# Truss-Power-V3-B.net
KiCad netlist of a schematic drawn in EAGLE
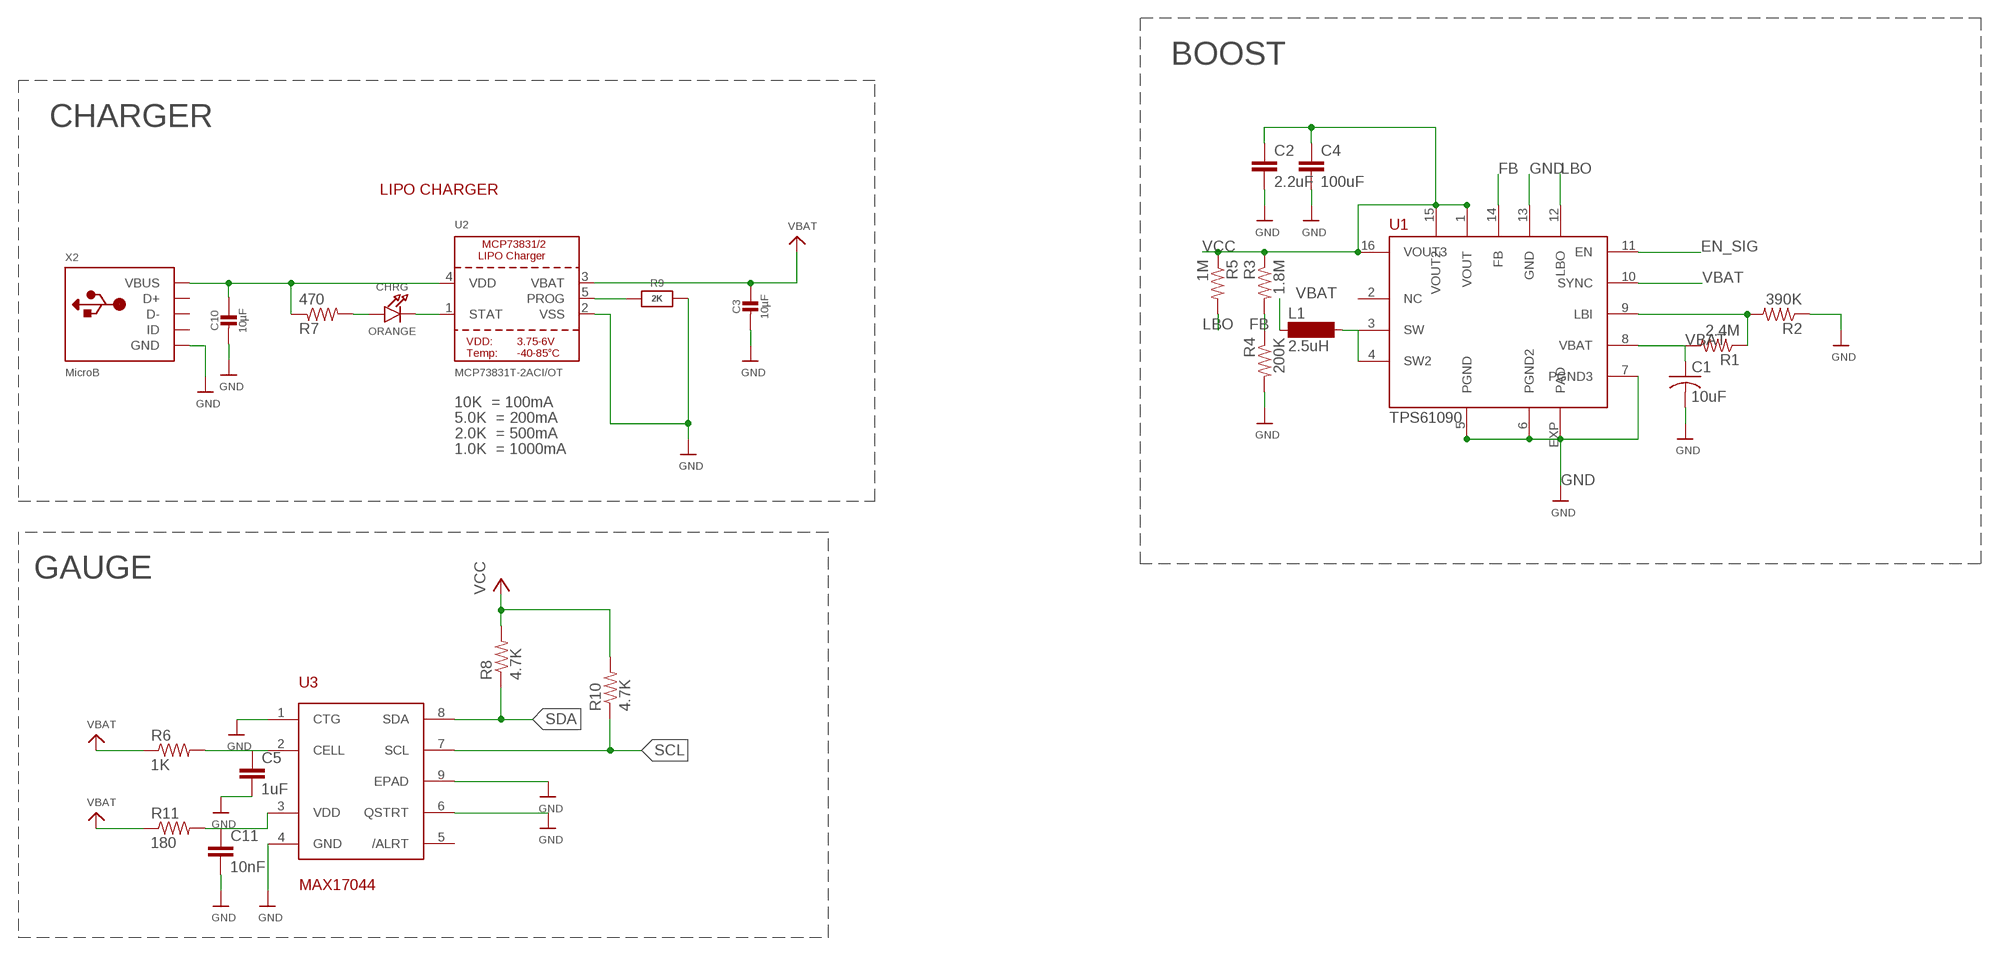
[diagram p0: schematic, sheet 1]
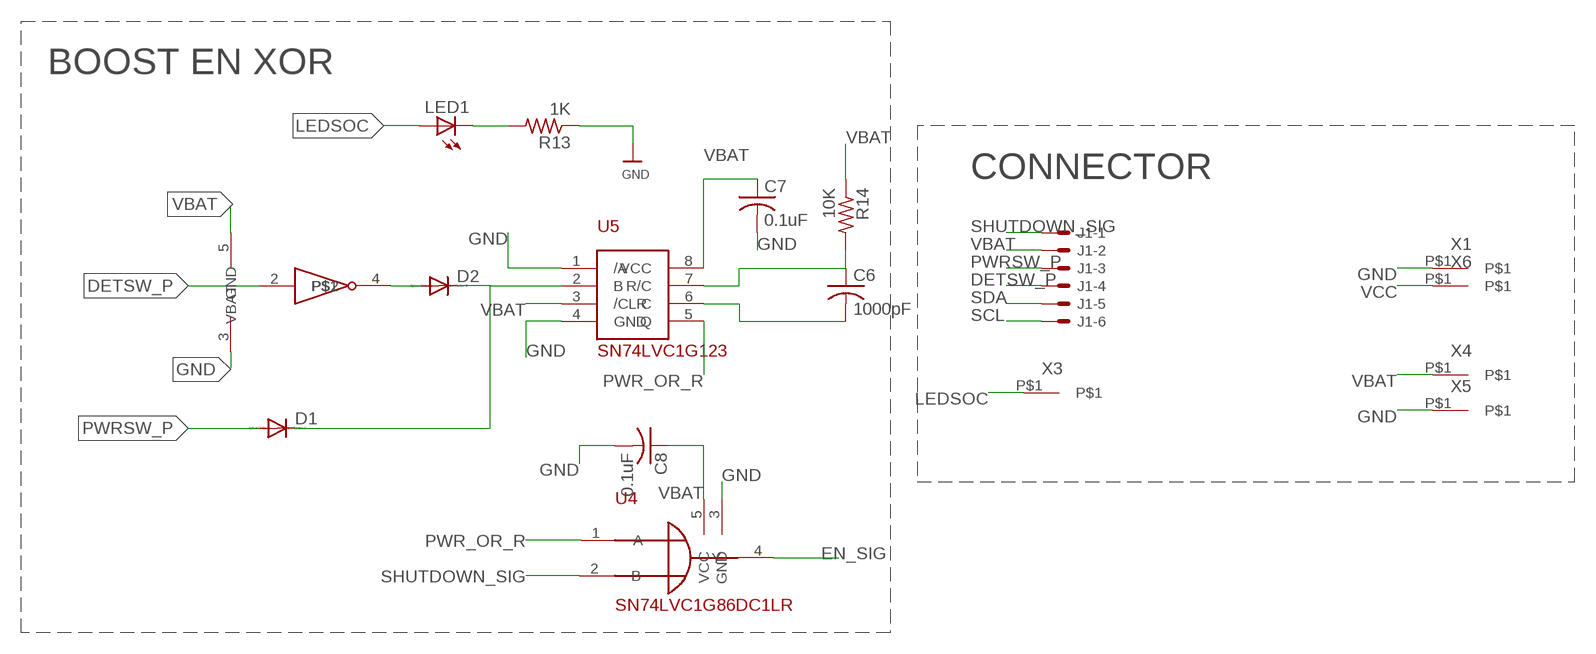
[diagram p1: schematic, sheet 2]

(export (version "E")
  (design (tool "Eeschema 10.0.6"))
  (components
    (comp (ref "C1")
      (value "10uF")
      (footprint "eagle-import:C0805K")
      (libsource (lib "eagle-import") (part "C-USC0805K"))
    )
    (comp (ref "C2")
      (value "2.2uF")
      (footprint "eagle-import:C0805K")
      (libsource (lib "eagle-import") (part "C-EUC0805K"))
    )
    (comp (ref "C3")
      (value "10µF")
      (footprint "eagle-import:0805-NO")
      (libsource (lib "eagle-import") (part "CAP_CERAMIC0805-NOOUTLINE"))
    )
    (comp (ref "C4")
      (value "100uF")
      (footprint "eagle-import:7343-METRIC")
      (libsource (lib "eagle-import") (part "TANT-CAP"))
    )
    (comp (ref "C5")
      (value "1uF")
      (footprint "eagle-import:C0603")
      (libsource (lib "eagle-import") (part "C-EUC0603"))
    )
    (comp (ref "C10")
      (value "10µF")
      (footprint "eagle-import:0805-NO")
      (libsource (lib "eagle-import") (part "CAP_CERAMIC0805-NOOUTLINE"))
    )
    (comp (ref "C11")
      (value "10nF")
      (footprint "eagle-import:C0603")
      (libsource (lib "eagle-import") (part "C-EUC0603"))
    )
    (comp (ref "CHRG")
      (value "ORANGE")
      (footprint "eagle-import:CHIPLED_0805_NOOUTLINE")
      (libsource (lib "eagle-import") (part "LED0805_NOOUTLINE"))
    )
    (comp (ref "L1")
      (value "2.5uH")
      (footprint "eagle-import:CDRH5D28")
      (libsource (lib "eagle-import") (part "CDRH5D28"))
    )
    (comp (ref "R1")
      (value "2.4M")
      (footprint "eagle-import:R0603")
      (libsource (lib "eagle-import") (part "R-US_R0603"))
    )
    (comp (ref "R2")
      (value "390K")
      (footprint "eagle-import:R0603")
      (libsource (lib "eagle-import") (part "R-US_R0603"))
    )
    (comp (ref "R3")
      (value "1.8M")
      (footprint "eagle-import:R0603")
      (libsource (lib "eagle-import") (part "R-US_R0603"))
    )
    (comp (ref "R4")
      (value "200K")
      (footprint "eagle-import:R0603")
      (libsource (lib "eagle-import") (part "R-US_R0603"))
    )
    (comp (ref "R5")
      (value "1M")
      (footprint "eagle-import:R0603")
      (libsource (lib "eagle-import") (part "R-US_R0603"))
    )
    (comp (ref "R6")
      (value "1K")
      (footprint "eagle-import:R0402")
      (libsource (lib "eagle-import") (part "resistor_R-US_R0402"))
    )
    (comp (ref "R7")
      (value "470")
      (footprint "eagle-import:R0402")
      (libsource (lib "eagle-import") (part "resistor_R-US_R0402"))
    )
    (comp (ref "R8")
      (value "4.7K")
      (footprint "eagle-import:R0402")
      (libsource (lib "eagle-import") (part "resistor_R-US_R0402"))
    )
    (comp (ref "R9")
      (value "2K")
      (footprint "eagle-import:0805-NO")
      (libsource (lib "eagle-import") (part "RESISTOR0805_NOOUTLINE"))
    )
    (comp (ref "R10")
      (value "4.7K")
      (footprint "eagle-import:R0402")
      (libsource (lib "eagle-import") (part "resistor_R-US_R0402"))
    )
    (comp (ref "R11")
      (value "180")
      (footprint "eagle-import:R0402")
      (libsource (lib "eagle-import") (part "resistor_R-US_R0402"))
    )
    (comp (ref "U1")
      (value "TPS61090")
      (footprint "eagle-import:TPS61090")
      (libsource (lib "eagle-import") (part "TPS61090"))
    )
    (comp (ref "U2")
      (value "MCP73831T-2ACI/OT")
      (footprint "eagle-import:SOT23-5")
      (libsource (lib "eagle-import") (part "MCP73831/2"))
    )
    (comp (ref "U3")
      (value "MAX17044")
      (footprint "eagle-import:TDFN")
      (libsource (lib "eagle-import") (part "MAX17044"))
    )
    (comp (ref "X2")
      (value "MicroB")
      (footprint "eagle-import:4UCONN_20329")
      (libsource (lib "eagle-import") (part "USBMICRO_20329"))
    )
    (comp (ref "C6")
      (value "1000pF")
      (footprint "eagle-import:C0402")
      (libsource (lib "eagle-import") (part "rcl_334_C-USC0402"))
    )
    (comp (ref "C7")
      (value "0.1uF")
      (footprint "eagle-import:C0603")
      (libsource (lib "eagle-import") (part "rcl_334_C-USC0603"))
    )
    (comp (ref "C8")
      (value "0.1uF")
      (footprint "eagle-import:C0603")
      (libsource (lib "eagle-import") (part "rcl_334_C-USC0603"))
    )
    (comp (ref "D1")
      (value "DIODE-SOD523")
      (footprint "eagle-import:SOD523")
      (libsource (lib "eagle-import") (part "DIODE-SOD523"))
    )
    (comp (ref "D2")
      (value "DIODE-SOD523")
      (footprint "eagle-import:SOD523")
      (libsource (lib "eagle-import") (part "DIODE-SOD523"))
    )
    (comp (ref "J1")
      (value "XF2L-0625-1")
      (footprint "eagle-import:XF2L-0625-1")
      (fields (field (name "MF") "OMRON COMPONENTS USA"))
      (libsource (lib "eagle-import") (part "XF2-06?25-1L"))
    )
    (comp (ref "LED1")
      (value "LEDCHIP-LED0603")
      (footprint "eagle-import:CHIP-LED0603")
      (libsource (lib "eagle-import") (part "LEDCHIP-LED0603"))
    )
    (comp (ref "R13")
      (value "1K")
      (footprint "eagle-import:R0402")
      (libsource (lib "eagle-import") (part "resistor_R-US_R0402"))
    )
    (comp (ref "R14")
      (value "10K")
      (footprint "eagle-import:R0402")
      (libsource (lib "eagle-import") (part "resistor_R-US_R0402"))
    )
    (comp (ref "U$16")
      (value "INVERTER-GATE")
      (footprint "eagle-import:SOC70-5")
      (libsource (lib "eagle-import") (part "INVERTER-GATE"))
    )
    (comp (ref "U4")
      (value "SN74LVC1G86DC1LR")
      (footprint "eagle-import:SOC70-5")
      (libsource (lib "eagle-import") (part "SN74LVC1G86DC1LR"))
    )
    (comp (ref "U5")
      (value "SN74LVC1G123")
      (footprint "eagle-import:SSOP8")
      (libsource (lib "eagle-import") (part "SN74LVC1G123"))
    )
    (comp (ref "X1")
      (value "CON-1PIN")
      (footprint "eagle-import:CON-1PIN")
      (libsource (lib "eagle-import") (part "CON-1PIN"))
    )
    (comp (ref "X3")
      (value "CON-1PINB")
      (footprint "eagle-import:CON-1PIN-B")
      (libsource (lib "eagle-import") (part "CON-1PINB"))
    )
    (comp (ref "X4")
      (value "CON-1PIN")
      (footprint "eagle-import:CON-1PIN")
      (libsource (lib "eagle-import") (part "CON-1PIN"))
    )
    (comp (ref "X5")
      (value "CON-1PIN")
      (footprint "eagle-import:CON-1PIN")
      (libsource (lib "eagle-import") (part "CON-1PIN"))
    )
    (comp (ref "X6")
      (value "CON-1PIN")
      (footprint "eagle-import:CON-1PIN")
      (libsource (lib "eagle-import") (part "CON-1PIN"))
    )
  )
  (nets
    (net (code "1") (name "DETSW_P") (class "Default")
      (node (ref "J1") (pin "4") (pinfunction "MS_4") (pintype "passive"))
      (node (ref "U$16") (pin "2") (pinfunction "P$1_2") (pintype "bidirectional"))
    )
    (net (code "2") (name "EN_SIG") (class "Default")
      (node (ref "U1") (pin "11") (pinfunction "EN_11") (pintype "bidirectional"))
      (node (ref "U4") (pin "4") (pinfunction "Y_4") (pintype "bidirectional"))
    )
    (net (code "3") (name "FB") (class "Default")
      (node (ref "R3") (pin "2") (pinfunction "2_2") (pintype "passive"))
      (node (ref "R4") (pin "1") (pinfunction "1_1") (pintype "passive"))
      (node (ref "U1") (pin "14") (pinfunction "FB_14") (pintype "bidirectional"))
    )
    (net (code "4") (name "GND") (class "Default")
      (node (ref "C1") (pin "2") (pinfunction "2_2") (pintype "passive"))
      (node (ref "C10") (pin "2") (pinfunction "2_2") (pintype "passive"))
      (node (ref "C11") (pin "2") (pinfunction "2_2") (pintype "passive"))
      (node (ref "C2") (pin "2") (pinfunction "2_2") (pintype "passive"))
      (node (ref "C3") (pin "2") (pinfunction "2_2") (pintype "passive"))
      (node (ref "C4") (pin "2") (pinfunction "2_2") (pintype "passive"))
      (node (ref "C5") (pin "2") (pinfunction "2_2") (pintype "passive"))
      (node (ref "C7") (pin "2") (pinfunction "2_2") (pintype "passive"))
      (node (ref "C8") (pin "2") (pinfunction "2_2") (pintype "passive"))
      (node (ref "R13") (pin "1") (pinfunction "1_1") (pintype "passive"))
      (node (ref "R2") (pin "1") (pinfunction "1_1") (pintype "passive"))
      (node (ref "R4") (pin "2") (pinfunction "2_2") (pintype "passive"))
      (node (ref "R9") (pin "2") (pinfunction "2_2") (pintype "passive"))
      (node (ref "U$16") (pin "3") (pinfunction "GND_3") (pintype "bidirectional"))
      (node (ref "U1") (pin "13") (pinfunction "GND_13") (pintype "bidirectional"))
      (node (ref "U1") (pin "5") (pinfunction "PGND_5") (pintype "bidirectional"))
      (node (ref "U1") (pin "6") (pinfunction "PGND2_6") (pintype "bidirectional"))
      (node (ref "U1") (pin "7") (pinfunction "PGND3_7") (pintype "bidirectional"))
      (node (ref "U1") (pin "EXP") (pinfunction "PAD_EXP") (pintype "bidirectional"))
      (node (ref "U2") (pin "2") (pinfunction "VSS_2") (pintype "power_in"))
      (node (ref "U3") (pin "1") (pinfunction "CTG_1") (pintype "bidirectional"))
      (node (ref "U3") (pin "4") (pinfunction "GND_4") (pintype "bidirectional"))
      (node (ref "U3") (pin "6") (pinfunction "QSTRT_6") (pintype "bidirectional"))
      (node (ref "U3") (pin "9") (pinfunction "EPAD_9") (pintype "bidirectional"))
      (node (ref "U4") (pin "3") (pinfunction "GND_3") (pintype "bidirectional"))
      (node (ref "U5") (pin "1") (pinfunction "/A_1") (pintype "bidirectional"))
      (node (ref "U5") (pin "4") (pinfunction "GND_4") (pintype "bidirectional"))
      (node (ref "X1") (pin "P$1") (pinfunction "P$1_P$1") (pintype "bidirectional"))
      (node (ref "X2") (pin "BASE@1") (pinfunction "GND_BASE@1") (pintype "power_in"))
      (node (ref "X2") (pin "BASE@2") (pinfunction "GND_BASE@2") (pintype "power_in"))
      (node (ref "X2") (pin "GND") (pinfunction "GND_GND") (pintype "power_in"))
      (node (ref "X2") (pin "SPRT@1") (pinfunction "GND_SPRT@1") (pintype "power_in"))
      (node (ref "X2") (pin "SPRT@2") (pinfunction "GND_SPRT@2") (pintype "power_in"))
      (node (ref "X2") (pin "SPRT@3") (pinfunction "GND_SPRT@3") (pintype "power_in"))
      (node (ref "X2") (pin "SPRT@4") (pinfunction "GND_SPRT@4") (pintype "power_in"))
      (node (ref "X5") (pin "P$1") (pinfunction "P$1_P$1") (pintype "bidirectional"))
    )
    (net (code "5") (name "LBO") (class "Default")
      (node (ref "R5") (pin "2") (pinfunction "2_2") (pintype "passive"))
      (node (ref "U1") (pin "12") (pinfunction "LBO_12") (pintype "bidirectional"))
    )
    (net (code "6") (name "LEDSOC") (class "Default")
      (node (ref "LED1") (pin "A") (pinfunction "A_A") (pintype "passive"))
      (node (ref "X3") (pin "P$1") (pinfunction "P$1_P$1") (pintype "bidirectional"))
    )
    (net (code "7") (name "Net-(CHRG-PadA)") (class "Default")
      (node (ref "CHRG") (pin "A") (pinfunction "A_A") (pintype "passive"))
      (node (ref "R7") (pin "2") (pinfunction "2_2") (pintype "passive"))
    )
    (net (code "8") (name "Net-(LED1-PadC)") (class "Default")
      (node (ref "LED1") (pin "C") (pinfunction "C_C") (pintype "passive"))
      (node (ref "R13") (pin "2") (pinfunction "2_2") (pintype "passive"))
    )
    (net (code "9") (name "Net-(U$16-P$2)") (class "Default")
      (node (ref "D2") (pin "A") (pinfunction "A_A") (pintype "passive"))
      (node (ref "U$16") (pin "4") (pinfunction "P$2_4") (pintype "bidirectional"))
    )
    (net (code "10") (name "Net-(U1-LBI)") (class "Default")
      (node (ref "R1") (pin "1") (pinfunction "1_1") (pintype "passive"))
      (node (ref "R2") (pin "2") (pinfunction "2_2") (pintype "passive"))
      (node (ref "U1") (pin "9") (pinfunction "LBI_9") (pintype "bidirectional"))
    )
    (net (code "11") (name "Net-(U1-SW)") (class "Default")
      (node (ref "L1") (pin "2") (pinfunction "2_2") (pintype "passive"))
      (node (ref "U1") (pin "3") (pinfunction "SW_3") (pintype "bidirectional"))
      (node (ref "U1") (pin "4") (pinfunction "SW2_4") (pintype "bidirectional"))
    )
    (net (code "12") (name "Net-(U2-PROG)") (class "Default")
      (node (ref "R9") (pin "1") (pinfunction "1_1") (pintype "passive"))
      (node (ref "U2") (pin "5") (pinfunction "PROG_5") (pintype "input"))
    )
    (net (code "13") (name "Net-(U2-STAT)") (class "Default")
      (node (ref "CHRG") (pin "C") (pinfunction "C_C") (pintype "passive"))
      (node (ref "U2") (pin "1") (pinfunction "STAT_1") (pintype "output"))
    )
    (net (code "14") (name "Net-(U2-VDD)") (class "Default")
      (node (ref "C10") (pin "1") (pinfunction "1_1") (pintype "passive"))
      (node (ref "R7") (pin "1") (pinfunction "1_1") (pintype "passive"))
      (node (ref "U2") (pin "4") (pinfunction "VDD_4") (pintype "power_in"))
      (node (ref "X2") (pin "VBUS") (pinfunction "VBUS_VBUS") (pintype "power_in"))
    )
    (net (code "15") (name "Net-(U3-CELL)") (class "Default")
      (node (ref "C5") (pin "1") (pinfunction "1_1") (pintype "passive"))
      (node (ref "R6") (pin "2") (pinfunction "2_2") (pintype "passive"))
      (node (ref "U3") (pin "2") (pinfunction "CELL_2") (pintype "bidirectional"))
    )
    (net (code "16") (name "Net-(U3-VDD)") (class "Default")
      (node (ref "C11") (pin "1") (pinfunction "1_1") (pintype "passive"))
      (node (ref "R11") (pin "2") (pinfunction "2_2") (pintype "passive"))
      (node (ref "U3") (pin "3") (pinfunction "VDD_3") (pintype "bidirectional"))
    )
    (net (code "17") (name "Net-(U5-B)") (class "Default")
      (node (ref "D1") (pin "C") (pinfunction "C_C") (pintype "passive"))
      (node (ref "D2") (pin "C") (pinfunction "C_C") (pintype "passive"))
      (node (ref "U5") (pin "2") (pinfunction "B_2") (pintype "bidirectional"))
    )
    (net (code "18") (name "Net-(U5-C)") (class "Default")
      (node (ref "C6") (pin "2") (pinfunction "2_2") (pintype "passive"))
      (node (ref "U5") (pin "6") (pinfunction "C_6") (pintype "bidirectional"))
    )
    (net (code "19") (name "Net-(U5-R{slash}C)") (class "Default")
      (node (ref "C6") (pin "1") (pinfunction "1_1") (pintype "passive"))
      (node (ref "R14") (pin "2") (pinfunction "2_2") (pintype "passive"))
      (node (ref "U5") (pin "7") (pinfunction "R/C_7") (pintype "bidirectional"))
    )
    (net (code "20") (name "PWRSW_P") (class "Default")
      (node (ref "D1") (pin "A") (pinfunction "A_A") (pintype "passive"))
      (node (ref "J1") (pin "3") (pinfunction "MS_3") (pintype "passive"))
    )
    (net (code "21") (name "PWR_OR_R") (class "Default")
      (node (ref "U4") (pin "1") (pinfunction "A_1") (pintype "bidirectional"))
      (node (ref "U5") (pin "5") (pinfunction "Q_5") (pintype "bidirectional"))
    )
    (net (code "22") (name "SCL") (class "Default")
      (node (ref "J1") (pin "6") (pinfunction "MS_6") (pintype "passive"))
      (node (ref "R10") (pin "1") (pinfunction "1_1") (pintype "passive"))
      (node (ref "U3") (pin "7") (pinfunction "SCL_7") (pintype "bidirectional"))
    )
    (net (code "23") (name "SDA") (class "Default")
      (node (ref "J1") (pin "5") (pinfunction "MS_5") (pintype "passive"))
      (node (ref "R8") (pin "1") (pinfunction "1_1") (pintype "passive"))
      (node (ref "U3") (pin "8") (pinfunction "SDA_8") (pintype "bidirectional"))
    )
    (net (code "24") (name "SHUTDOWN_SIG") (class "Default")
      (node (ref "J1") (pin "1") (pinfunction "MS_1") (pintype "passive"))
      (node (ref "U4") (pin "2") (pinfunction "B_2") (pintype "bidirectional"))
    )
    (net (code "25") (name "VBAT") (class "Default")
      (node (ref "C1") (pin "1") (pinfunction "1_1") (pintype "passive"))
      (node (ref "C3") (pin "1") (pinfunction "1_1") (pintype "passive"))
      (node (ref "C7") (pin "1") (pinfunction "1_1") (pintype "passive"))
      (node (ref "C8") (pin "1") (pinfunction "1_1") (pintype "passive"))
      (node (ref "J1") (pin "2") (pinfunction "MS_2") (pintype "passive"))
      (node (ref "L1") (pin "1") (pinfunction "1_1") (pintype "passive"))
      (node (ref "R1") (pin "2") (pinfunction "2_2") (pintype "passive"))
      (node (ref "R11") (pin "1") (pinfunction "1_1") (pintype "passive"))
      (node (ref "R14") (pin "1") (pinfunction "1_1") (pintype "passive"))
      (node (ref "R6") (pin "1") (pinfunction "1_1") (pintype "passive"))
      (node (ref "U$16") (pin "5") (pinfunction "VBAT_5") (pintype "bidirectional"))
      (node (ref "U1") (pin "10") (pinfunction "SYNC_10") (pintype "bidirectional"))
      (node (ref "U1") (pin "8") (pinfunction "VBAT_8") (pintype "bidirectional"))
      (node (ref "U2") (pin "3") (pinfunction "VBAT_3") (pintype "power_in"))
      (node (ref "U4") (pin "5") (pinfunction "VCC_5") (pintype "bidirectional"))
      (node (ref "U5") (pin "3") (pinfunction "/CLR_3") (pintype "bidirectional"))
      (node (ref "U5") (pin "8") (pinfunction "VCC_8") (pintype "bidirectional"))
      (node (ref "X4") (pin "P$1") (pinfunction "P$1_P$1") (pintype "bidirectional"))
    )
    (net (code "26") (name "VCC") (class "Default")
      (node (ref "C2") (pin "1") (pinfunction "1_1") (pintype "passive"))
      (node (ref "C4") (pin "1") (pinfunction "1_1") (pintype "passive"))
      (node (ref "R10") (pin "2") (pinfunction "2_2") (pintype "passive"))
      (node (ref "R3") (pin "1") (pinfunction "1_1") (pintype "passive"))
      (node (ref "R5") (pin "1") (pinfunction "1_1") (pintype "passive"))
      (node (ref "R8") (pin "2") (pinfunction "2_2") (pintype "passive"))
      (node (ref "U1") (pin "1") (pinfunction "VOUT_1") (pintype "bidirectional"))
      (node (ref "U1") (pin "15") (pinfunction "VOUT2_15") (pintype "bidirectional"))
      (node (ref "U1") (pin "16") (pinfunction "VOUT3_16") (pintype "bidirectional"))
      (node (ref "X6") (pin "P$1") (pinfunction "P$1_P$1") (pintype "bidirectional"))
    )
    (net (code "27") (name "unconnected-(U1-NC-Pad2)") (class "Default")
      (node (ref "U1") (pin "2") (pinfunction "NC_2") (pintype "bidirectional"))
    )
    (net (code "28") (name "unconnected-(U3-{slash}ALRT-Pad5)") (class "Default")
      (node (ref "U3") (pin "5") (pinfunction "/ALRT_5") (pintype "bidirectional"))
    )
    (net (code "29") (name "unconnected-(X2-PadD+)") (class "Default")
      (node (ref "X2") (pin "D+") (pinfunction "D+_D+") (pintype "bidirectional"))
    )
    (net (code "30") (name "unconnected-(X2-PadD-)") (class "Default")
      (node (ref "X2") (pin "D-") (pinfunction "D-_D-") (pintype "bidirectional"))
    )
    (net (code "31") (name "unconnected-(X2-PadID)") (class "Default")
      (node (ref "X2") (pin "ID") (pinfunction "ID_ID") (pintype "bidirectional"))
    )
  )
)
